# 03_EFR32xG1x_DISC_REF_DES_A00_Efr32Signa.net
KiCad netlist of a schematic drawn in Altium Designer
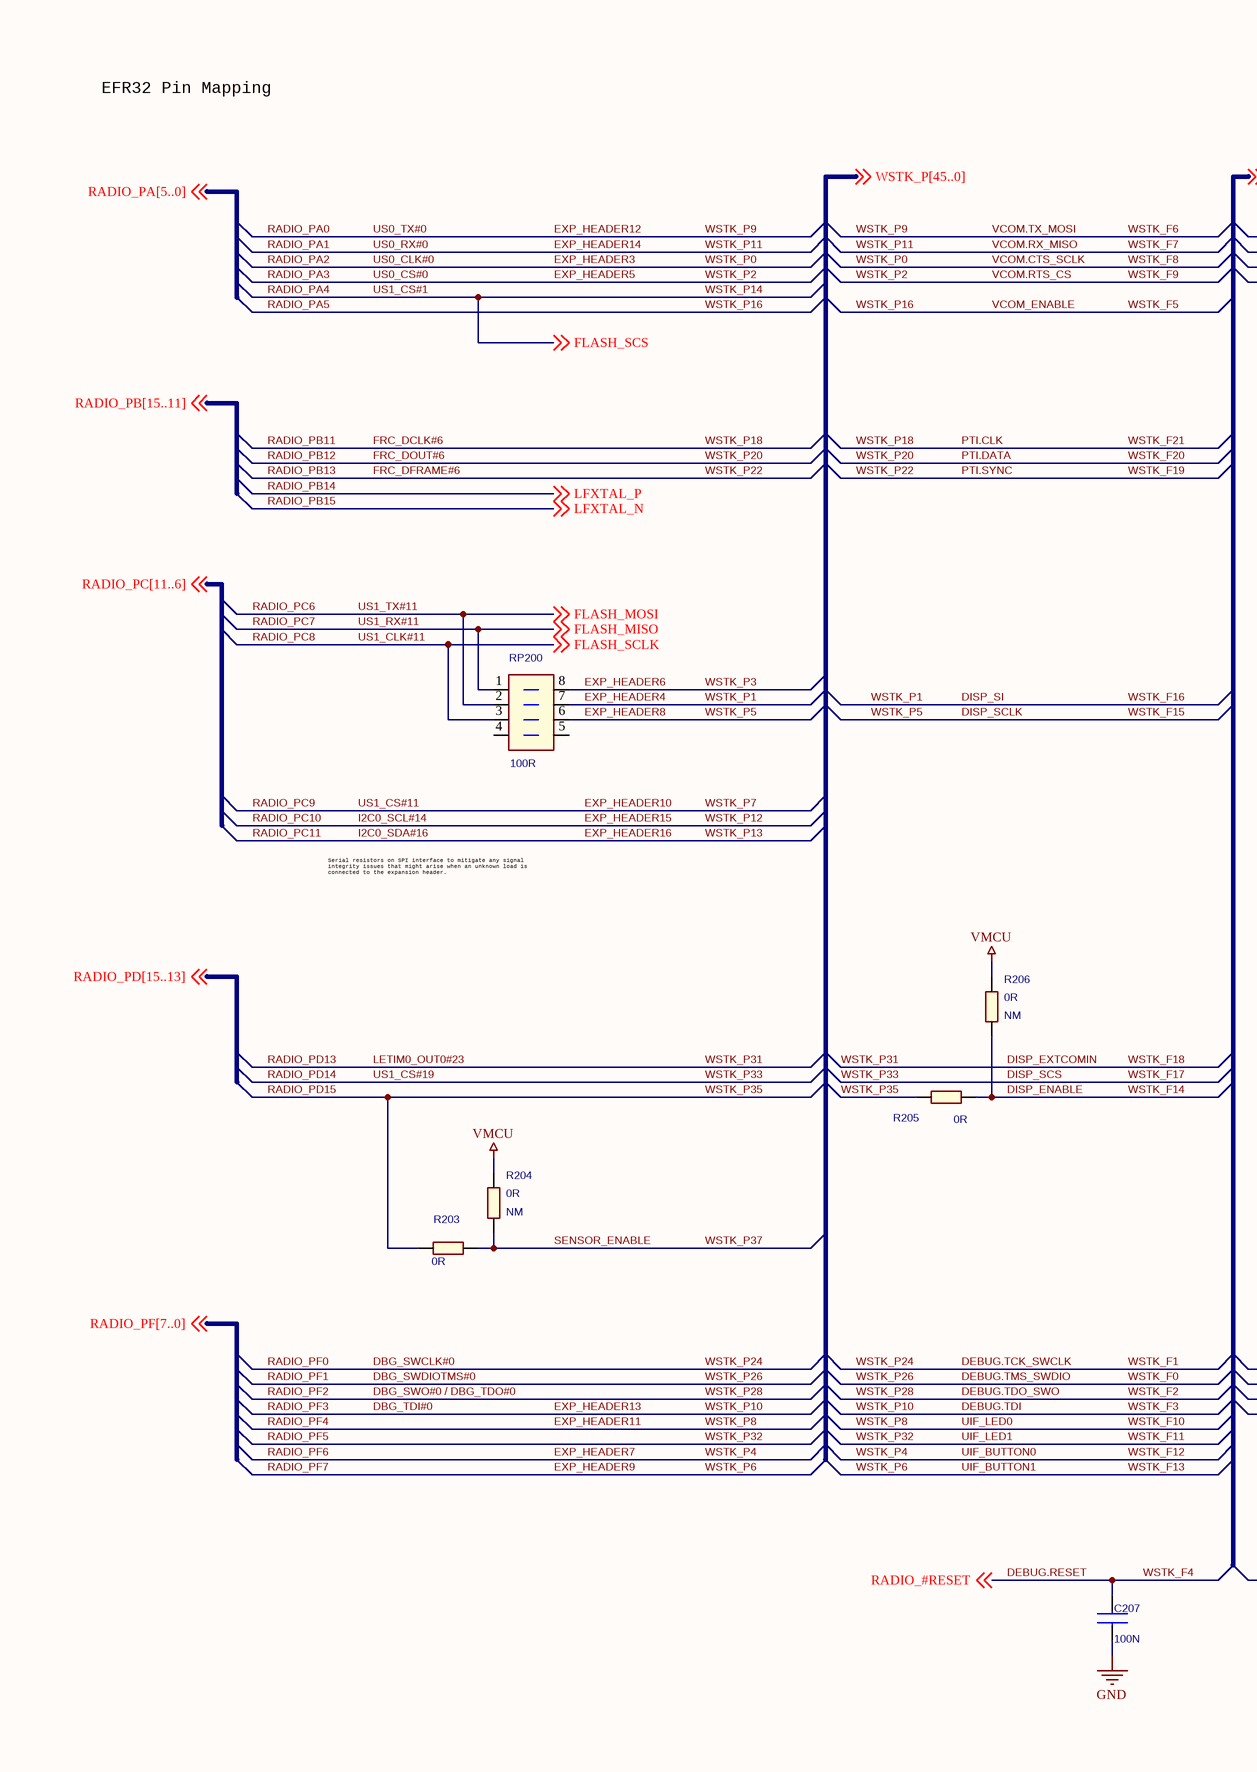
[diagram p0: 03_EFR32xG1x_DISC_REF_DES_A00_Efr32Signal.SchDoc, left]
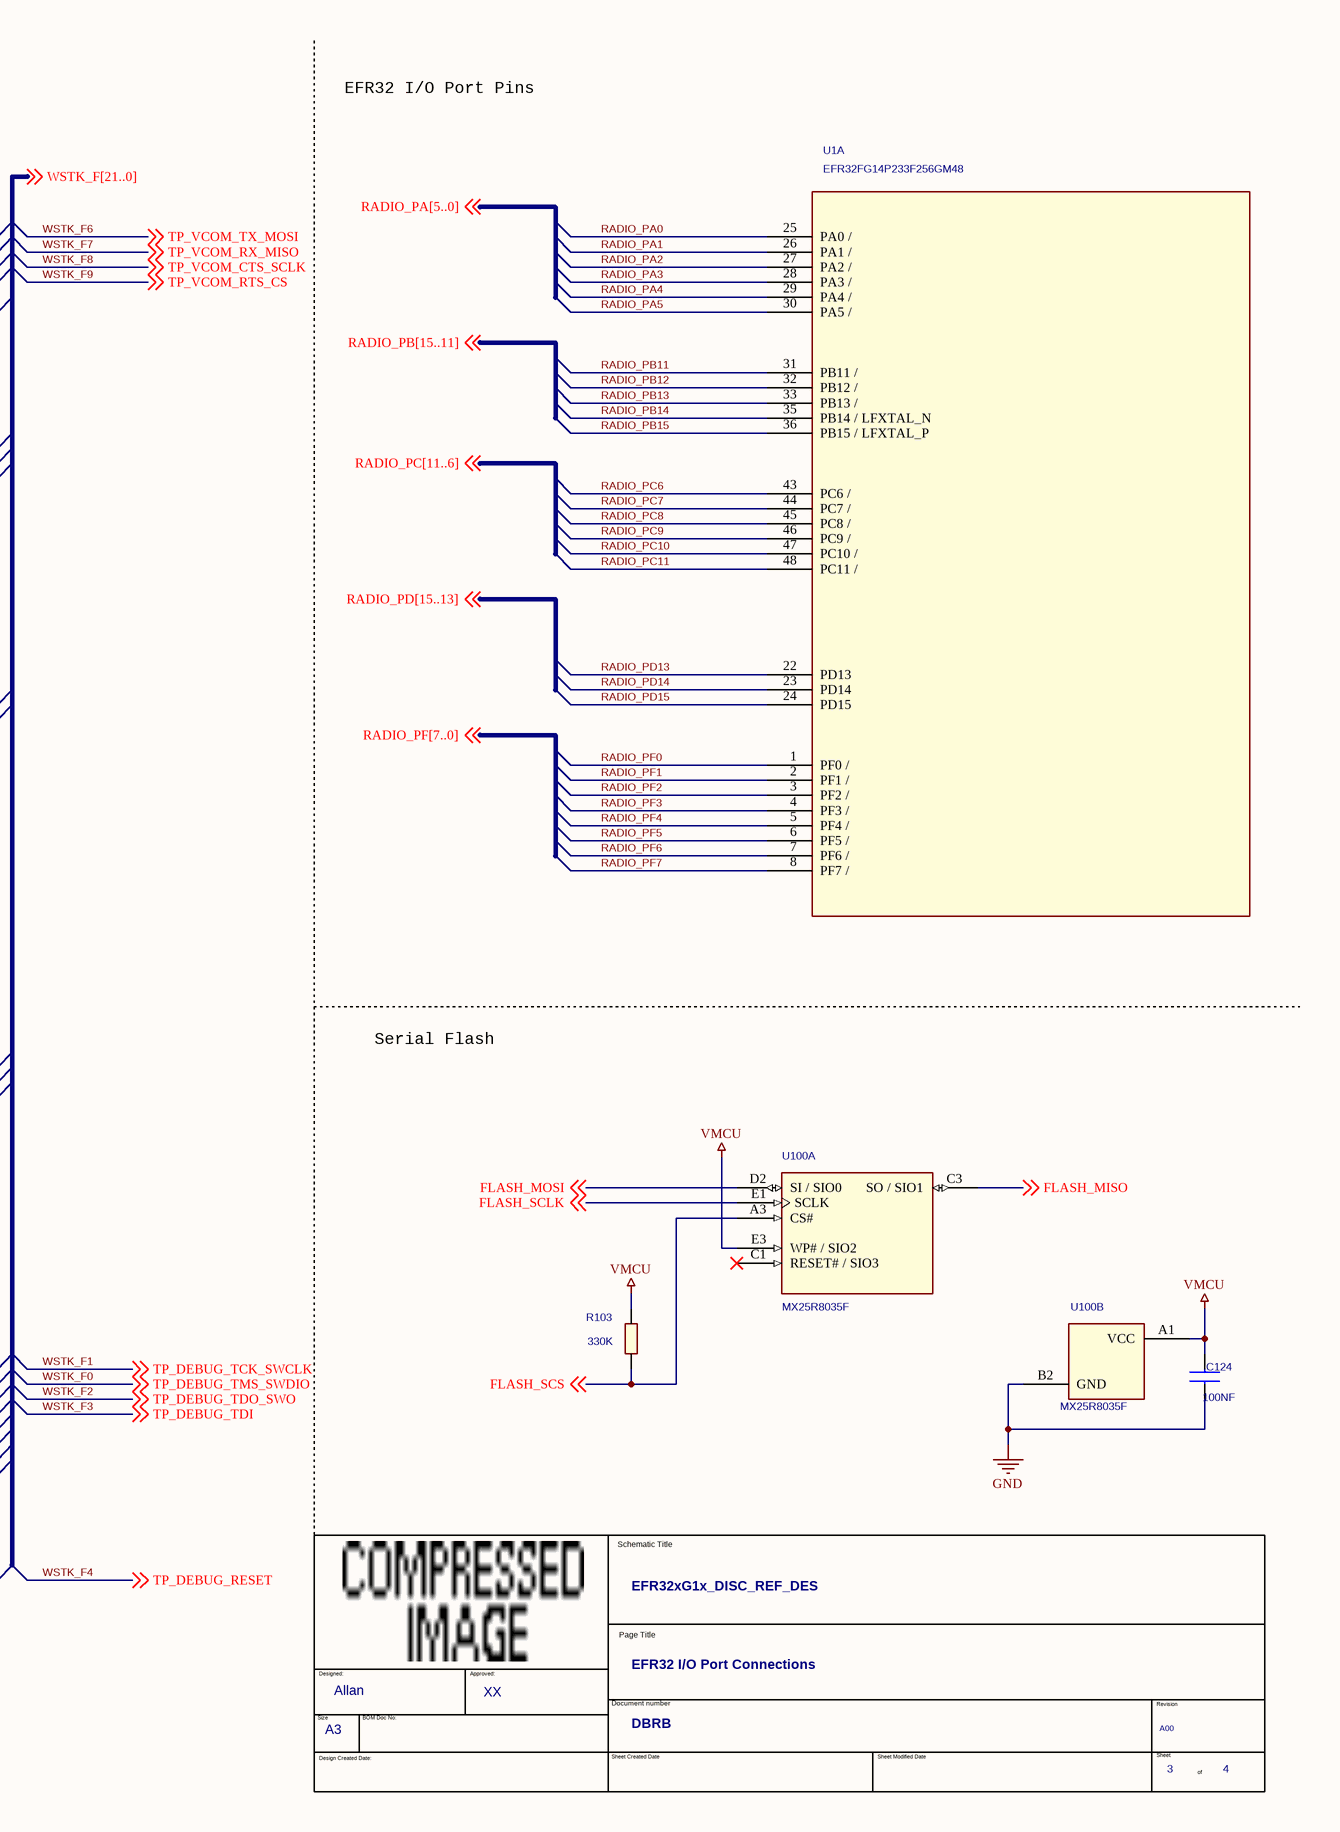
[diagram p1: 03_EFR32xG1x_DISC_REF_DES_A00_Efr32Signal.SchDoc, right]

(export (version "E")
  (design (tool "Eeschema 10.0.6"))
  (components
    (comp (ref "C124")
      (value "100NF")
      (footprint "C0402_L")
      (fields (field (name "TOLERANCE") "10%"))
      (libsource (lib "*") (part "C0402"))
    )
    (comp (ref "C207")
      (value "100N")
      (footprint "C0402_L")
      (fields (field (name "TOLERANCE") "10%"))
      (libsource (lib "*") (part "C0402"))
    )
    (comp (ref "R103") (value "330K") (footprint "R0402_L") (libsource (lib "*") (part "R0402")))
    (comp (ref "R203") (value "0R") (footprint "R0402_L") (libsource (lib "") (part "R0402_1")))
    (comp (ref "R204")
      (value "0R")
      (footprint "R0402_L")
      (fields (field (name "NOT MOUNTED") "NM"))
      (libsource (lib "*") (part "R0402"))
    )
    (comp (ref "R205") (value "0R") (footprint "R0402_L") (libsource (lib "") (part "R0402_1")))
    (comp (ref "R206")
      (value "0R")
      (footprint "R0402_L")
      (fields (field (name "NOT MOUNTED") "NM"))
      (libsource (lib "*") (part "R0402"))
    )
    (comp (ref "RP200")
      (value "100R")
      (footprint "RES_MNR04-8")
      (fields (field (name "MFG") "ROHM"))
      (libsource (lib "*") (part "MNR04M0APJ101"))
    )
    (comp (ref "U1")
      (value "EFR32FG14P233F256GM48")
      (footprint "QFN48_M050_SQ7.0_EP_SL_L")
      (fields (field (name "MFG") "Silicon Labs"))
      (libsource (lib "*") (part "EFR32-DUALBAND-QFN48"))
    )
    (comp (ref "U100")
      (value "MX25R8035F")
      (footprint "BGA8_M040_1.24x1.75_WLCSP")
      (fields (field (name "MFG") "Macronix"))
      (libsource (lib "*") (part "MX25R8035"))
    )
  )
  (nets
    (net (code "1") (name "FLASH_MISO") (class "Default")
      (node (ref "RP200") (pin "1") (pinfunction "R11_1") (pintype "passive"))
      (node (ref "U1") (pin "44") (pinfunction "PC7_/_44") (pintype "passive"))
      (node (ref "U100") (pin "C3") (pinfunction "SO_/_SIO1_C3") (pintype "bidirectional"))
    )
    (net (code "2") (name "FLASH_MOSI") (class "Default")
      (node (ref "RP200") (pin "2") (pinfunction "R12_2") (pintype "passive"))
      (node (ref "U1") (pin "43") (pinfunction "PC6_/_43") (pintype "passive"))
      (node (ref "U100") (pin "D2") (pinfunction "SI_/_SIO0_D2") (pintype "bidirectional"))
    )
    (net (code "3") (name "FLASH_SCLK") (class "Default")
      (node (ref "RP200") (pin "3") (pinfunction "R13_3") (pintype "passive"))
      (node (ref "U1") (pin "45") (pinfunction "PC8_/_45") (pintype "passive"))
      (node (ref "U100") (pin "E1") (pinfunction "SCLK_E1") (pintype "input"))
    )
    (net (code "4") (name "FLASH_SCS") (class "Default")
      (node (ref "R103") (pin "2") (pinfunction "2_2") (pintype "passive"))
      (node (ref "U1") (pin "29") (pinfunction "PA4_/_29") (pintype "passive"))
      (node (ref "U100") (pin "A3") (pinfunction "CS#_A3") (pintype "input"))
    )
    (net (code "5") (name "GND") (class "Default")
      (node (ref "C124") (pin "2") (pinfunction "2_2") (pintype "passive"))
      (node (ref "C207") (pin "2") (pinfunction "2_2") (pintype "passive"))
      (node (ref "U100") (pin "B2") (pinfunction "GND_B2") (pintype "power_in"))
    )
    (net (code "6") (name "LFXTAL_N") (class "Default")
      (node (ref "U1") (pin "36") (pinfunction "PB15_/_LFXTAL_P_36") (pintype "passive"))
    )
    (net (code "7") (name "LFXTAL_P") (class "Default")
      (node (ref "U1") (pin "35") (pinfunction "PB14_/_LFXTAL_N_35") (pintype "passive"))
    )
    (net (code "8") (name "RADIO_#RESET") (class "Default")
      (node (ref "C207") (pin "1") (pinfunction "1_1") (pintype "passive"))
    )
    (net (code "14") (name "TP_DEBUG_TCK_SWCLK") (class "Default")
      (node (ref "U1") (pin "1") (pinfunction "PF0_/_1") (pintype "passive"))
    )
    (net (code "15") (name "TP_DEBUG_TDI") (class "Default")
      (node (ref "U1") (pin "4") (pinfunction "PF3_/_4") (pintype "passive"))
    )
    (net (code "16") (name "TP_DEBUG_TDO_SWO") (class "Default")
      (node (ref "U1") (pin "3") (pinfunction "PF2_/_3") (pintype "passive"))
    )
    (net (code "17") (name "TP_DEBUG_TMS_SWDIO") (class "Default")
      (node (ref "U1") (pin "2") (pinfunction "PF1_/_2") (pintype "passive"))
    )
    (net (code "18") (name "TP_VCOM_CTS_SCLK") (class "Default")
      (node (ref "U1") (pin "27") (pinfunction "PA2_/_27") (pintype "passive"))
    )
    (net (code "19") (name "TP_VCOM_RTS_CS") (class "Default")
      (node (ref "U1") (pin "28") (pinfunction "PA3_/_28") (pintype "passive"))
    )
    (net (code "20") (name "TP_VCOM_RX_MISO") (class "Default")
      (node (ref "U1") (pin "26") (pinfunction "PA1_/_26") (pintype "passive"))
    )
    (net (code "21") (name "TP_VCOM_TX_MOSI") (class "Default")
      (node (ref "U1") (pin "25") (pinfunction "PA0_/_25") (pintype "passive"))
    )
    (net (code "22") (name "VMCU") (class "Default")
      (node (ref "C124") (pin "1") (pinfunction "1_1") (pintype "passive"))
      (node (ref "R103") (pin "1") (pinfunction "1_1") (pintype "passive"))
      (node (ref "R204") (pin "1") (pinfunction "1_1") (pintype "passive"))
      (node (ref "R206") (pin "1") (pinfunction "1_1") (pintype "passive"))
      (node (ref "U100") (pin "A1") (pinfunction "VCC_A1") (pintype "power_in"))
      (node (ref "U100") (pin "E3") (pinfunction "WP#_/_SIO2_E3") (pintype "input"))
    )
    (net (code "23") (name "WSTK_F5") (class "Default")
      (node (ref "U1") (pin "30") (pinfunction "PA5_/_30") (pintype "passive"))
    )
    (net (code "24") (name "WSTK_F10") (class "Default")
      (node (ref "U1") (pin "5") (pinfunction "PF4_/_5") (pintype "passive"))
    )
    (net (code "25") (name "WSTK_F11") (class "Default")
      (node (ref "U1") (pin "6") (pinfunction "PF5_/_6") (pintype "passive"))
    )
    (net (code "26") (name "WSTK_F12") (class "Default")
      (node (ref "U1") (pin "7") (pinfunction "PF6_/_7") (pintype "passive"))
    )
    (net (code "27") (name "WSTK_F13") (class "Default")
      (node (ref "U1") (pin "8") (pinfunction "PF7_/_8") (pintype "passive"))
    )
    (net (code "28") (name "WSTK_F14") (class "Default")
      (node (ref "R205") (pin "2") (pinfunction "2_2") (pintype "passive"))
      (node (ref "R206") (pin "2") (pinfunction "2_2") (pintype "passive"))
    )
    (net (code "29") (name "WSTK_F15") (class "Default")
      (node (ref "RP200") (pin "6") (pinfunction "R16_6") (pintype "passive"))
    )
    (net (code "30") (name "WSTK_F16") (class "Default")
      (node (ref "RP200") (pin "7") (pinfunction "R17_7") (pintype "passive"))
    )
    (net (code "31") (name "WSTK_F17") (class "Default")
      (node (ref "U1") (pin "23") (pinfunction "PD14_23") (pintype "passive"))
    )
    (net (code "32") (name "WSTK_F18") (class "Default")
      (node (ref "U1") (pin "22") (pinfunction "PD13_22") (pintype "passive"))
    )
    (net (code "33") (name "WSTK_F19") (class "Default")
      (node (ref "U1") (pin "33") (pinfunction "PB13_/_33") (pintype "passive"))
    )
    (net (code "34") (name "WSTK_F20") (class "Default")
      (node (ref "U1") (pin "32") (pinfunction "PB12_/_32") (pintype "passive"))
    )
    (net (code "35") (name "WSTK_F21") (class "Default")
      (node (ref "U1") (pin "31") (pinfunction "PB11_/_31") (pintype "passive"))
    )
    (net (code "37") (name "WSTK_P3") (class "Default")
      (node (ref "RP200") (pin "8") (pinfunction "R18_8") (pintype "passive"))
    )
    (net (code "38") (name "WSTK_P7") (class "Default")
      (node (ref "U1") (pin "46") (pinfunction "PC9_/_46") (pintype "passive"))
    )
    (net (code "39") (name "WSTK_P12") (class "Default")
      (node (ref "U1") (pin "47") (pinfunction "PC10_/_47") (pintype "passive"))
    )
    (net (code "40") (name "WSTK_P13") (class "Default")
      (node (ref "U1") (pin "48") (pinfunction "PC11_/_48") (pintype "passive"))
    )
    (net (code "41") (name "WSTK_P35") (class "Default")
      (node (ref "R203") (pin "1") (pinfunction "1_1") (pintype "passive"))
      (node (ref "R205") (pin "1") (pinfunction "1_1") (pintype "passive"))
      (node (ref "U1") (pin "24") (pinfunction "PD15_24") (pintype "passive"))
    )
    (net (code "42") (name "WSTK_P37") (class "Default")
      (node (ref "R203") (pin "2") (pinfunction "2_2") (pintype "passive"))
      (node (ref "R204") (pin "2") (pinfunction "2_2") (pintype "passive"))
    )
    (net (code "44") (name "unconnected-(RP200-R14-Pad4)") (class "Default")
      (node (ref "RP200") (pin "4") (pinfunction "R14_4") (pintype "passive"))
    )
    (net (code "45") (name "unconnected-(RP200-R15-Pad5)") (class "Default")
      (node (ref "RP200") (pin "5") (pinfunction "R15_5") (pintype "passive"))
    )
    (net (code "46") (name "unconnected-(U100A-RESET#_{slash}_SIO3-PadC1)") (class "Default")
      (node (ref "U100") (pin "C1") (pinfunction "RESET#_/_SIO3_C1") (pintype "input+no_connect"))
    )
  )
)
